# MaxAir_Smart_Home_Gateway_WT21-ET01_-_v0.net
KiCad netlist of a schematic drawn in EAGLE
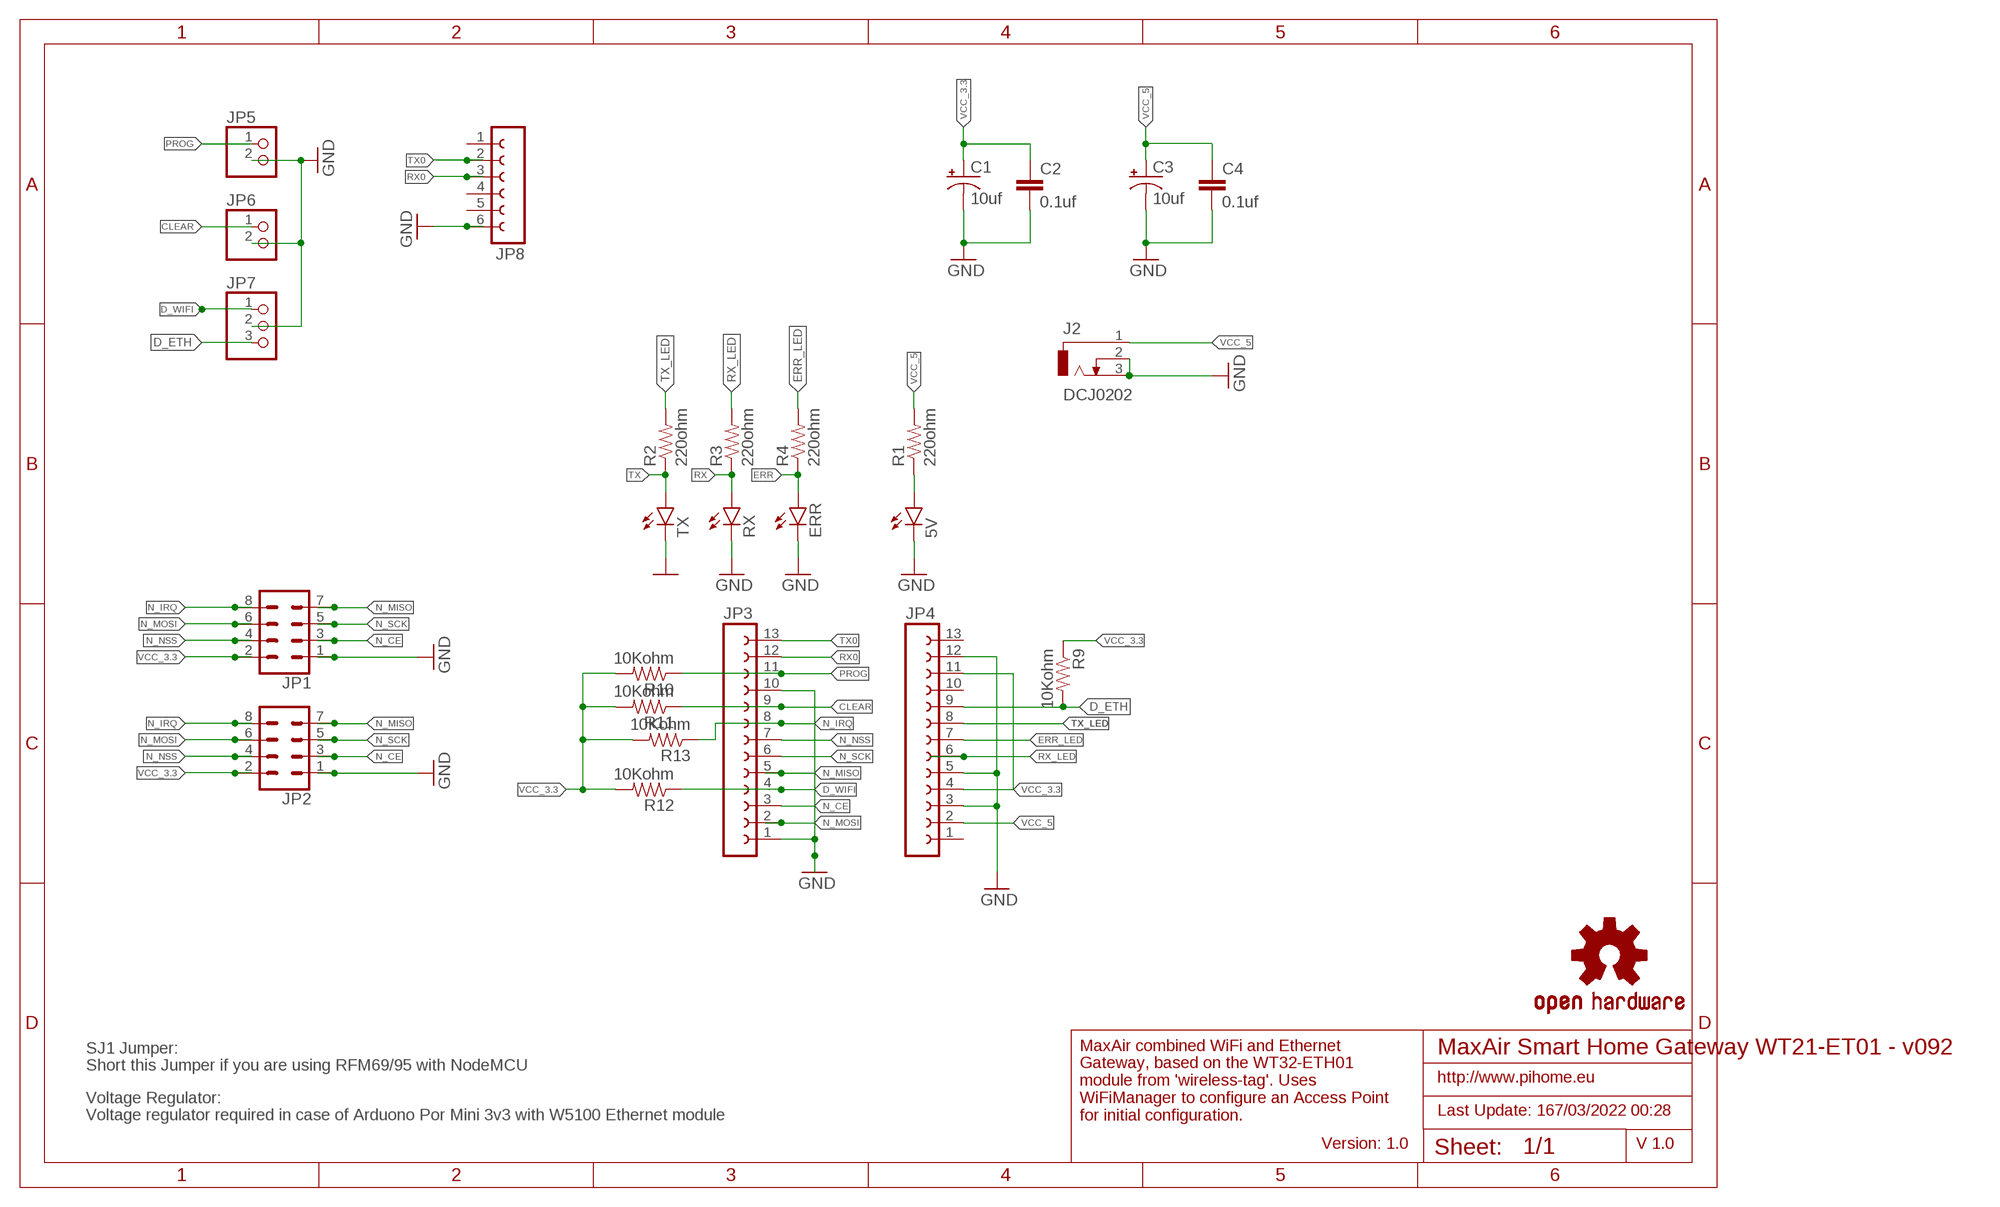
[diagram p0: schematic, sheet 1]

(export (version "E")
  (design (tool "Eeschema 10.0.6"))
  (components
    (comp (ref "5V")
      (value "LED3MM")
      (footprint "eagle-import:LED3MM")
      (libsource (lib "eagle-import") (part "LED3MM"))
    )
    (comp (ref "C1")
      (value "10uf")
      (footprint "eagle-import:CPOL-RADIAL-10UF-25V-KIT")
      (libsource (lib "eagle-import") (part "10UF-25V-20%(PTH)KIT"))
    )
    (comp (ref "C2")
      (value "0.1uf")
      (footprint "eagle-import:CAP-PTH-SMALL-KIT")
      (libsource (lib "eagle-import") (part "0.1UF-50V-20%(PTH)KIT-EZ"))
    )
    (comp (ref "C3")
      (value "10uf")
      (footprint "eagle-import:CPOL-RADIAL-10UF-25V-KIT")
      (libsource (lib "eagle-import") (part "10UF-25V-20%(PTH)KIT"))
    )
    (comp (ref "C4")
      (value "0.1uf")
      (footprint "eagle-import:CAP-PTH-SMALL-KIT")
      (libsource (lib "eagle-import") (part "0.1UF-50V-20%(PTH)KIT-EZ"))
    )
    (comp (ref "ERR")
      (value "LED3MM")
      (footprint "eagle-import:LED3MM")
      (libsource (lib "eagle-import") (part "LED3MM"))
    )
    (comp (ref "J2")
      (value "DCJ0202")
      (footprint "eagle-import:DCJ0202")
      (libsource (lib "eagle-import") (part "DCJ0202"))
    )
    (comp (ref "JP1")
      (value "CONN_04X2")
      (footprint "eagle-import:2X4")
      (libsource (lib "eagle-import") (part "CONN_04X2"))
    )
    (comp (ref "JP2")
      (value "CONN_04X2")
      (footprint "eagle-import:2X4")
      (libsource (lib "eagle-import") (part "CONN_04X2"))
    )
    (comp (ref "JP3")
      (value "FE13-1")
      (footprint "eagle-import:FE13")
      (libsource (lib "eagle-import") (part "FE13-1"))
    )
    (comp (ref "JP4")
      (value "FE13-1")
      (footprint "eagle-import:FE13")
      (libsource (lib "eagle-import") (part "FE13-1"))
    )
    (comp (ref "JP5")
      (value "PINHD-1X2")
      (footprint "eagle-import:1X02")
      (libsource (lib "eagle-import") (part "PINHD-1X2"))
    )
    (comp (ref "JP6")
      (value "PINHD-1X2")
      (footprint "eagle-import:1X02")
      (libsource (lib "eagle-import") (part "PINHD-1X2"))
    )
    (comp (ref "JP7")
      (value "PINHD-1X3")
      (footprint "eagle-import:1X03")
      (libsource (lib "eagle-import") (part "PINHD-1X3"))
    )
    (comp (ref "JP8")
      (value "FE06-1")
      (footprint "eagle-import:FE06")
      (libsource (lib "eagle-import") (part "FE06-1"))
    )
    (comp (ref "LOGO1")
      (value "OSHW-LOGOMINI")
      (footprint "eagle-import:OSHW-LOGO-MINI")
      (libsource (lib "eagle-import") (part "OSHW-LOGOMINI"))
    )
    (comp (ref "R1")
      (value "220ohm")
      (footprint "eagle-import:AXIAL-0.3")
      (libsource (lib "eagle-import") (part "RESISTORAXIAL-0.3"))
    )
    (comp (ref "R2")
      (value "220ohm")
      (footprint "eagle-import:AXIAL-0.3")
      (libsource (lib "eagle-import") (part "RESISTORAXIAL-0.3"))
    )
    (comp (ref "R3")
      (value "220ohm")
      (footprint "eagle-import:AXIAL-0.3")
      (libsource (lib "eagle-import") (part "RESISTORAXIAL-0.3"))
    )
    (comp (ref "R4")
      (value "220ohm")
      (footprint "eagle-import:AXIAL-0.3")
      (libsource (lib "eagle-import") (part "RESISTORAXIAL-0.3"))
    )
    (comp (ref "R9")
      (value "10Kohm")
      (footprint "eagle-import:AXIAL-0.3")
      (libsource (lib "eagle-import") (part "RESISTORAXIAL-0.3"))
    )
    (comp (ref "R10")
      (value "10Kohm")
      (footprint "eagle-import:AXIAL-0.3")
      (libsource (lib "eagle-import") (part "RESISTORAXIAL-0.3"))
    )
    (comp (ref "R11")
      (value "10Kohm")
      (footprint "eagle-import:AXIAL-0.3")
      (libsource (lib "eagle-import") (part "RESISTORAXIAL-0.3"))
    )
    (comp (ref "R12")
      (value "10Kohm")
      (footprint "eagle-import:AXIAL-0.3")
      (libsource (lib "eagle-import") (part "RESISTORAXIAL-0.3"))
    )
    (comp (ref "R13")
      (value "10Kohm")
      (footprint "eagle-import:AXIAL-0.3")
      (libsource (lib "eagle-import") (part "RESISTORAXIAL-0.3"))
    )
    (comp (ref "RX")
      (value "LED3MM")
      (footprint "eagle-import:LED3MM")
      (libsource (lib "eagle-import") (part "LED3MM"))
    )
    (comp (ref "TX")
      (value "LED3MM")
      (footprint "eagle-import:LED3MM")
      (libsource (lib "eagle-import") (part "LED3MM"))
    )
  )
  (nets
    (net (code "1") (name "CLEAR") (class "Default")
      (node (ref "JP3") (pin "9") (pinfunction "9_9") (pintype "passive"))
      (node (ref "JP6") (pin "1") (pinfunction "1_1") (pintype "passive"))
      (node (ref "R11") (pin "P$1") (pinfunction "1_P$1") (pintype "passive"))
    )
    (net (code "2") (name "D_ETH") (class "Default")
      (node (ref "JP4") (pin "9") (pinfunction "9_9") (pintype "passive"))
      (node (ref "JP7") (pin "3") (pinfunction "3_3") (pintype "passive"))
      (node (ref "R9") (pin "P$2") (pinfunction "2_P$2") (pintype "passive"))
    )
    (net (code "3") (name "D_WIFI") (class "Default")
      (node (ref "JP3") (pin "4") (pinfunction "4_4") (pintype "passive"))
      (node (ref "JP7") (pin "1") (pinfunction "1_1") (pintype "passive"))
      (node (ref "R12") (pin "P$1") (pinfunction "1_P$1") (pintype "passive"))
    )
    (net (code "4") (name "ERR") (class "Default")
      (node (ref "ERR") (pin "A") (pinfunction "A_A") (pintype "passive"))
      (node (ref "R4") (pin "P$1") (pinfunction "1_P$1") (pintype "passive"))
    )
    (net (code "5") (name "ERR_LED") (class "Default")
      (node (ref "JP4") (pin "7") (pinfunction "7_7") (pintype "passive"))
      (node (ref "R4") (pin "P$2") (pinfunction "2_P$2") (pintype "passive"))
    )
    (net (code "6") (name "GND") (class "Default")
      (node (ref "5V") (pin "K") (pinfunction "C_K") (pintype "passive"))
      (node (ref "C1") (pin "2") (pinfunction "-_2") (pintype "passive"))
      (node (ref "C2") (pin "2") (pinfunction "2_2") (pintype "passive"))
      (node (ref "C3") (pin "2") (pinfunction "-_2") (pintype "passive"))
      (node (ref "C4") (pin "2") (pinfunction "2_2") (pintype "passive"))
      (node (ref "ERR") (pin "K") (pinfunction "C_K") (pintype "passive"))
      (node (ref "J2") (pin "2") (pinfunction "2_2") (pintype "passive"))
      (node (ref "J2") (pin "3") (pinfunction "3_3") (pintype "passive"))
      (node (ref "JP1") (pin "1") (pinfunction "1_1") (pintype "passive"))
      (node (ref "JP2") (pin "1") (pinfunction "1_1") (pintype "passive"))
      (node (ref "JP3") (pin "1") (pinfunction "1_1") (pintype "passive"))
      (node (ref "JP3") (pin "10") (pinfunction "10_10") (pintype "passive"))
      (node (ref "JP4") (pin "12") (pinfunction "12_12") (pintype "passive"))
      (node (ref "JP4") (pin "3") (pinfunction "3_3") (pintype "passive"))
      (node (ref "JP4") (pin "5") (pinfunction "5_5") (pintype "passive"))
      (node (ref "JP5") (pin "2") (pinfunction "2_2") (pintype "passive"))
      (node (ref "JP6") (pin "2") (pinfunction "2_2") (pintype "passive"))
      (node (ref "JP7") (pin "2") (pinfunction "2_2") (pintype "passive"))
      (node (ref "JP8") (pin "6") (pinfunction "6_6") (pintype "passive"))
      (node (ref "RX") (pin "K") (pinfunction "C_K") (pintype "passive"))
      (node (ref "TX") (pin "K") (pinfunction "C_K") (pintype "passive"))
    )
    (net (code "7") (name "N_CE") (class "Default")
      (node (ref "JP1") (pin "3") (pinfunction "3_3") (pintype "passive"))
      (node (ref "JP2") (pin "3") (pinfunction "3_3") (pintype "passive"))
      (node (ref "JP3") (pin "3") (pinfunction "3_3") (pintype "passive"))
    )
    (net (code "8") (name "N_IRQ") (class "Default")
      (node (ref "JP1") (pin "8") (pinfunction "8_8") (pintype "passive"))
      (node (ref "JP2") (pin "8") (pinfunction "8_8") (pintype "passive"))
      (node (ref "JP3") (pin "8") (pinfunction "8_8") (pintype "passive"))
      (node (ref "R13") (pin "P$1") (pinfunction "1_P$1") (pintype "passive"))
    )
    (net (code "9") (name "N_MISO") (class "Default")
      (node (ref "JP1") (pin "7") (pinfunction "7_7") (pintype "passive"))
      (node (ref "JP2") (pin "7") (pinfunction "7_7") (pintype "passive"))
      (node (ref "JP3") (pin "5") (pinfunction "5_5") (pintype "passive"))
    )
    (net (code "10") (name "N_MOSI") (class "Default")
      (node (ref "JP1") (pin "6") (pinfunction "6_6") (pintype "passive"))
      (node (ref "JP2") (pin "6") (pinfunction "6_6") (pintype "passive"))
      (node (ref "JP3") (pin "2") (pinfunction "2_2") (pintype "passive"))
    )
    (net (code "11") (name "N_NSS") (class "Default")
      (node (ref "JP1") (pin "4") (pinfunction "4_4") (pintype "passive"))
      (node (ref "JP2") (pin "4") (pinfunction "4_4") (pintype "passive"))
      (node (ref "JP3") (pin "7") (pinfunction "7_7") (pintype "passive"))
    )
    (net (code "12") (name "N_SCK") (class "Default")
      (node (ref "JP1") (pin "5") (pinfunction "5_5") (pintype "passive"))
      (node (ref "JP2") (pin "5") (pinfunction "5_5") (pintype "passive"))
      (node (ref "JP3") (pin "6") (pinfunction "6_6") (pintype "passive"))
    )
    (net (code "13") (name "Net-(R1-1)") (class "Default")
      (node (ref "5V") (pin "A") (pinfunction "A_A") (pintype "passive"))
      (node (ref "R1") (pin "P$1") (pinfunction "1_P$1") (pintype "passive"))
    )
    (net (code "14") (name "PROG") (class "Default")
      (node (ref "JP3") (pin "11") (pinfunction "11_11") (pintype "passive"))
      (node (ref "JP5") (pin "1") (pinfunction "1_1") (pintype "passive"))
      (node (ref "R10") (pin "P$1") (pinfunction "1_P$1") (pintype "passive"))
    )
    (net (code "15") (name "RX") (class "Default")
      (node (ref "R3") (pin "P$1") (pinfunction "1_P$1") (pintype "passive"))
      (node (ref "RX") (pin "A") (pinfunction "A_A") (pintype "passive"))
    )
    (net (code "16") (name "RX0") (class "Default")
      (node (ref "JP3") (pin "12") (pinfunction "12_12") (pintype "passive"))
      (node (ref "JP8") (pin "3") (pinfunction "3_3") (pintype "passive"))
    )
    (net (code "17") (name "RX_LED") (class "Default")
      (node (ref "JP4") (pin "6") (pinfunction "6_6") (pintype "passive"))
      (node (ref "R3") (pin "P$2") (pinfunction "2_P$2") (pintype "passive"))
    )
    (net (code "18") (name "TX") (class "Default")
      (node (ref "R2") (pin "P$1") (pinfunction "1_P$1") (pintype "passive"))
      (node (ref "TX") (pin "A") (pinfunction "A_A") (pintype "passive"))
    )
    (net (code "19") (name "TX0") (class "Default")
      (node (ref "JP3") (pin "13") (pinfunction "13_13") (pintype "passive"))
      (node (ref "JP8") (pin "2") (pinfunction "2_2") (pintype "passive"))
    )
    (net (code "20") (name "TX_LED") (class "Default")
      (node (ref "JP4") (pin "8") (pinfunction "8_8") (pintype "passive"))
      (node (ref "R2") (pin "P$2") (pinfunction "2_P$2") (pintype "passive"))
    )
    (net (code "21") (name "VCC_3.3") (class "Default")
      (node (ref "C1") (pin "1") (pinfunction "+_1") (pintype "passive"))
      (node (ref "C2") (pin "1") (pinfunction "1_1") (pintype "passive"))
      (node (ref "JP1") (pin "2") (pinfunction "2_2") (pintype "passive"))
      (node (ref "JP2") (pin "2") (pinfunction "2_2") (pintype "passive"))
      (node (ref "JP4") (pin "11") (pinfunction "11_11") (pintype "passive"))
      (node (ref "JP4") (pin "4") (pinfunction "4_4") (pintype "passive"))
      (node (ref "R10") (pin "P$2") (pinfunction "2_P$2") (pintype "passive"))
      (node (ref "R11") (pin "P$2") (pinfunction "2_P$2") (pintype "passive"))
      (node (ref "R12") (pin "P$2") (pinfunction "2_P$2") (pintype "passive"))
      (node (ref "R13") (pin "P$2") (pinfunction "2_P$2") (pintype "passive"))
      (node (ref "R9") (pin "P$1") (pinfunction "1_P$1") (pintype "passive"))
    )
    (net (code "22") (name "VCC_5") (class "Default")
      (node (ref "C3") (pin "1") (pinfunction "+_1") (pintype "passive"))
      (node (ref "C4") (pin "1") (pinfunction "1_1") (pintype "passive"))
      (node (ref "J2") (pin "1") (pinfunction "1_1") (pintype "passive"))
      (node (ref "JP4") (pin "2") (pinfunction "2_2") (pintype "passive"))
      (node (ref "R1") (pin "P$2") (pinfunction "2_P$2") (pintype "passive"))
    )
    (net (code "23") (name "unconnected-(JP4-Pad1)") (class "Default")
      (node (ref "JP4") (pin "1") (pinfunction "1_1") (pintype "passive"))
    )
    (net (code "24") (name "unconnected-(JP4-Pad10)") (class "Default")
      (node (ref "JP4") (pin "10") (pinfunction "10_10") (pintype "passive"))
    )
    (net (code "25") (name "unconnected-(JP4-Pad13)") (class "Default")
      (node (ref "JP4") (pin "13") (pinfunction "13_13") (pintype "passive"))
    )
    (net (code "26") (name "unconnected-(JP8-Pad1)") (class "Default")
      (node (ref "JP8") (pin "1") (pinfunction "1_1") (pintype "passive"))
    )
    (net (code "27") (name "unconnected-(JP8-Pad4)") (class "Default")
      (node (ref "JP8") (pin "4") (pinfunction "4_4") (pintype "passive"))
    )
    (net (code "28") (name "unconnected-(JP8-Pad5)") (class "Default")
      (node (ref "JP8") (pin "5") (pinfunction "5_5") (pintype "passive"))
    )
  )
)
